# MCU.net
KiCad netlist of a schematic drawn in Altium Designer
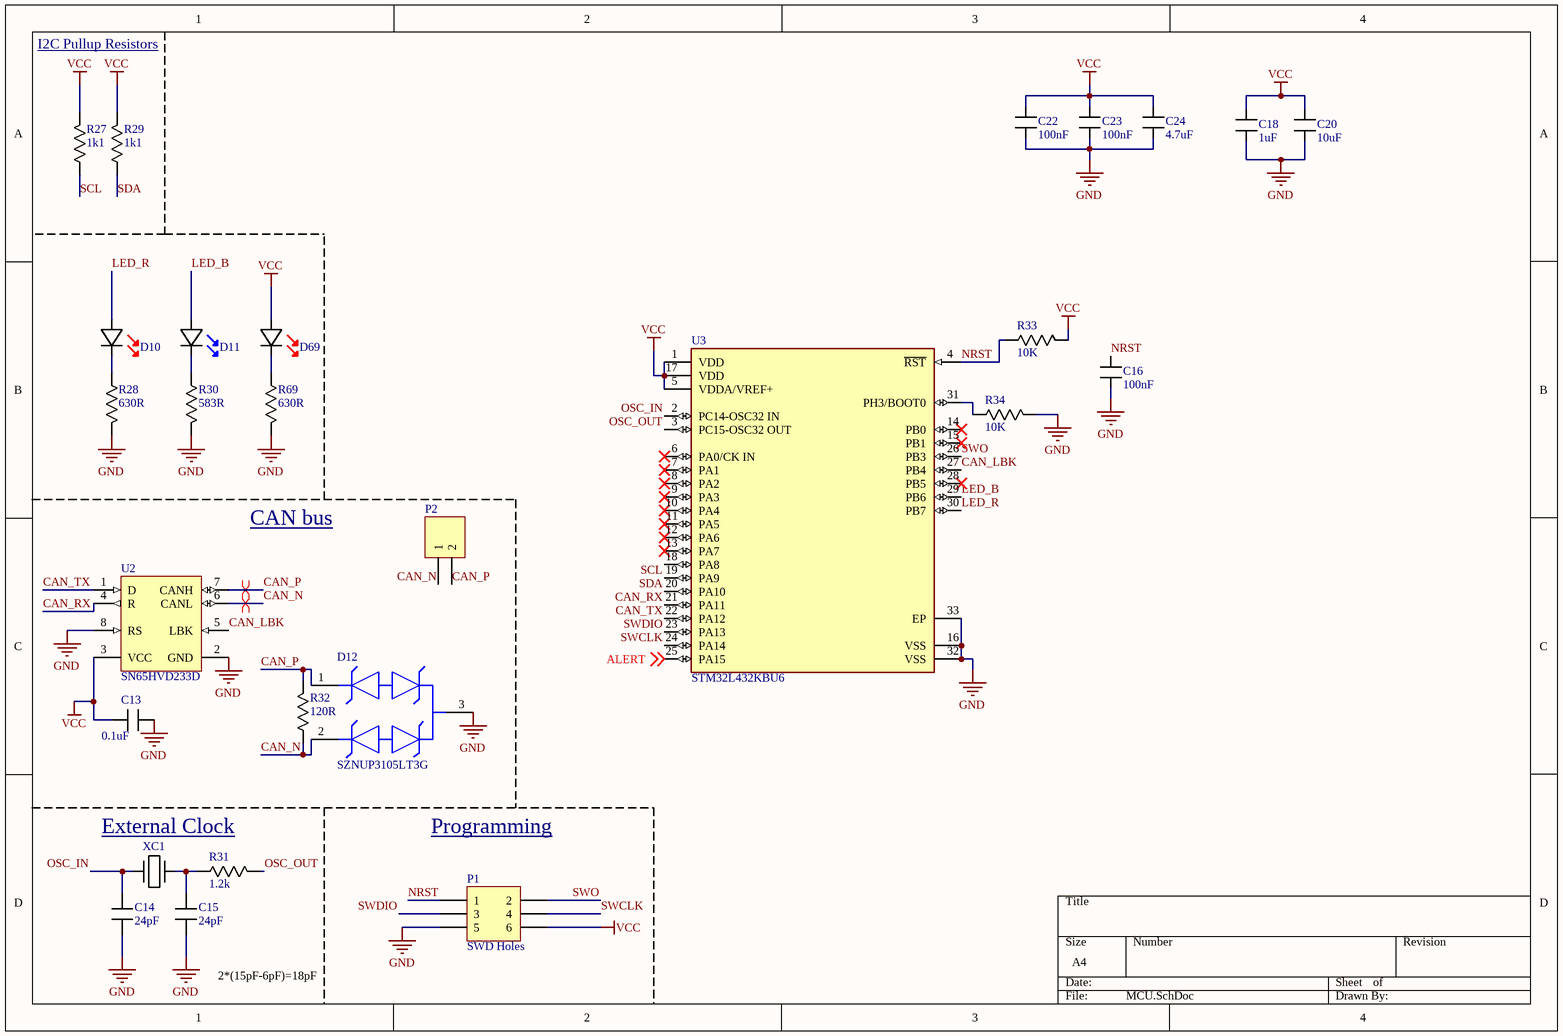
[diagram p0: MCU.SchDoc]

(export (version "E")
  (design (tool "Eeschema 10.0.6"))
  (components
    (comp (ref "C13")
      (value "0.1uF")
      (footprint "C_0603")
      (description "Capacitor")
      (fields
        (field (name "MANUFACTURER") "Kyocera AVX")
        (field (name "MANUFACTURER PART NUMBER") "06035C104JAT4A")
      )
      (libsource (lib "") (part "Capacitor_1"))
    )
    (comp (ref "C14")
      (value "24pF")
      (footprint "C_0603")
      (description "Cap Ceramic 24pF 100V C0G 1% Pad SMD 0603 125°C Ultra Low ESR T/R")
      (fields
        (field (name "MANUFACTURER") "Kyocera AVX")
        (field (name "MANUFACTURER PART NUMBER") "06031U240FAT2A")
      )
      (libsource (lib "") (part "Capacitor_1"))
    )
    (comp (ref "C15")
      (value "24pF")
      (footprint "C_0603")
      (description "Cap Ceramic 24pF 100V C0G 1% Pad SMD 0603 125°C Ultra Low ESR T/R")
      (fields
        (field (name "MANUFACTURER") "Kyocera AVX")
        (field (name "MANUFACTURER PART NUMBER") "06031U240FAT2A")
      )
      (libsource (lib "") (part "Capacitor_1"))
    )
    (comp (ref "C16")
      (value "100nF")
      (footprint "C_0603")
      (description "CAP CER 0.1UF 50V X7R 0603")
      (fields
        (field (name "MANUFACTURER") "KEMET")
        (field (name "MANUFACTURER PART NUMBER") "C0603X104K5RAC7411")
      )
      (libsource (lib "Passives") (part "Capacitor"))
    )
    (comp (ref "C18")
      (value "1uF")
      (footprint "C_0603")
      (description "Capacitor")
      (fields
        (field (name "MANUFACTURER") "KEMET")
        (field (name "MANUFACTURER PART NUMBER") "C0603C105K9RAC7411")
      )
      (libsource (lib "Passives") (part "Capacitor"))
    )
    (comp (ref "C20")
      (value "10uF")
      (footprint "C_0603")
      (description "0603, 6.3V, X5R, 10 uF ± 10 %, T&R Q200 multilayer ceramic capacitor")
      (fields
        (field (name "MANUFACTURER") "Taiyo Yuden")
        (field (name "MANUFACTURER PART NUMBER") "JMK107ABJ106KAHT")
      )
      (libsource (lib "Passives") (part "Capacitor"))
    )
    (comp (ref "C22")
      (value "100nF")
      (footprint "C_0603")
      (description "CAP CER 0.1UF 50V X7R 0603")
      (fields
        (field (name "MANUFACTURER") "KEMET")
        (field (name "MANUFACTURER PART NUMBER") "C0603X104K5RAC7411")
      )
      (libsource (lib "Passives") (part "Capacitor"))
    )
    (comp (ref "C23")
      (value "100nF")
      (footprint "C_0603")
      (description "CAP CER 0.1UF 50V X7R 0603")
      (fields
        (field (name "MANUFACTURER") "KEMET")
        (field (name "MANUFACTURER PART NUMBER") "C0603X104K5RAC7411")
      )
      (libsource (lib "Passives") (part "Capacitor"))
    )
    (comp (ref "C24")
      (value "4.7uF")
      (footprint "C_0603")
      (description "Cap Ceramic 4.7uF 6.3V X7R 10% Pad SMD 0603 125°C T/R")
      (fields
        (field (name "MANUFACTURER") "Taiyo Yuden")
        (field (name "MANUFACTURER PART NUMBER") "JMK107BB7475KA-T")
      )
      (libsource (lib "Passives") (part "Capacitor"))
    )
    (comp (ref "D10")
      (value "150060RS55040")
      (footprint "150060xS55040")
      (description "SMT Mono-color Chip LED Diffused")
      (libsource (lib "LV BMS SchLib") (part "150060RS55040"))
    )
    (comp (ref "D11")
      (value "150060BS55040")
      (footprint "150060xS55040")
      (description "LED BLUE DIFFUSED 0603 SMD")
      (fields (field (name "MANUFACTURER") "Wurth Electronics"))
      (libsource (lib "LV BMS SchLib") (part "150060BS55040"))
    )
    (comp (ref "D12")
      (value "SZNUP3105LT3G")
      (footprint "FP-318-08-MFG")
      (description "TVS DIODE 32V 66V SOT23-3")
      (fields
        (field (name "MANUFACTURER") "ON Semiconductor")
        (field (name "OCTOPART") "https://octopart.com/sznup3105lt3g-on+semiconductor-54318507")
      )
      (libsource (lib "Altium Content Vault") (part "ce38d3c06daa81fdde8c05c38ac5c9a"))
    )
    (comp (ref "D69")
      (value "150060RS55040")
      (footprint "150060xS55040")
      (description "SMT Mono-color Chip LED Diffused")
      (libsource (lib "LV BMS SchLib") (part "150060RS55040"))
    )
    (comp (ref "P1")
      (value "SWD Holes")
      (footprint "2*3 2.54mm header")
      (description "Header, 3-Pin, Dual row")
      (fields (field (name "PUBLISHER") "Altium Limited"))
      (libsource (lib "Miscellaneous Connectors") (part "MHDR2X3"))
    )
    (comp (ref "P2")
      (value "Nothing")
      (footprint "2x1 2.54MM PITCH")
      (description "Header, 2-Pin")
      (fields (field (name "PUBLISHER") "Altium Limited"))
      (libsource (lib "Miscellaneous Connectors") (part "MHDR1X2"))
    )
    (comp (ref "R27")
      (value "1k1")
      (footprint "R-0603")
      (description "Resistor")
      (fields
        (field (name "MANUFACTURER") "Vishay")
        (field (name "MANUFACTURER PART NUMBER") "CRCW06031K10JNEAC")
      )
      (libsource (lib "Passives") (part "Resistor"))
    )
    (comp (ref "R28")
      (value "630R")
      (footprint "R-0603")
      (description "High Precision-High Stability Chip Resistor Thin Film 0603 583Ohm 0.5% Paper T/R")
      (fields
        (field (name "MANUFACTURER") "Yageo")
        (field (name "MANUFACTURER PART NUMBER") "RT0603DRE07583RL")
      )
      (libsource (lib "Passives") (part "Resistor"))
    )
    (comp (ref "R29")
      (value "1k1")
      (footprint "R-0603")
      (description "Resistor")
      (fields
        (field (name "MANUFACTURER") "Vishay")
        (field (name "MANUFACTURER PART NUMBER") "CRCW06031K10JNEAC")
      )
      (libsource (lib "Passives") (part "Resistor"))
    )
    (comp (ref "R30")
      (value "583R")
      (footprint "R-0603")
      (description "High Precision-High Stability Chip Resistor Thin Film 0603 583Ohm 0.5% Paper T/R")
      (fields
        (field (name "MANUFACTURER") "Yageo")
        (field (name "MANUFACTURER PART NUMBER") "RT0603DRE07583RL")
      )
      (libsource (lib "Passives") (part "Resistor"))
    )
    (comp (ref "R31")
      (value "1.2k")
      (footprint "R-0603")
      (description "Resistor")
      (libsource (lib "Passives") (part "Resistor"))
    )
    (comp (ref "R32")
      (value "120R")
      (footprint "R-0603")
      (description "Bus termination resistor")
      (fields (field (name "Comment") "Dont populate"))
      (libsource (lib "Passives") (part "Resistor"))
    )
    (comp (ref "R33")
      (value "10K")
      (footprint "R-0603")
      (description "Resistor")
      (fields
        (field (name "MANUFACTURER") "Bourns")
        (field (name "MANUFACTURER PART NUMBER") "CMP0603AFX-1002ELF")
      )
      (libsource (lib "Passives") (part "Resistor"))
    )
    (comp (ref "R34")
      (value "10K")
      (footprint "R-0603")
      (description "Resistor")
      (fields
        (field (name "MANUFACTURER") "Bourns")
        (field (name "MANUFACTURER PART NUMBER") "CMP0603AFX-1002ELF")
      )
      (libsource (lib "Passives") (part "Resistor"))
    )
    (comp (ref "R69")
      (value "630R")
      (footprint "R-0603")
      (description "High Precision-High Stability Chip Resistor Thin Film 0603 583Ohm 0.5% Paper T/R")
      (fields
        (field (name "MANUFACTURER") "Yageo")
        (field (name "MANUFACTURER PART NUMBER") "RT0603DRE07583RL")
      )
      (libsource (lib "Passives") (part "Resistor"))
    )
    (comp (ref "U2")
      (value "SN65HVD233D")
      (footprint "D0008A_N")
      (fields (field (name "MANUFACTURER") "Texas Instruments"))
      (libsource (lib "Altium Content Vault") (part "TI-SN65HVD233-SOIC_D-8"))
    )
    (comp (ref "U3")
      (value "STM32L432KBU6")
      (footprint "FP-UFQFPN32-A0B8-MFG")
      (description "IC MCU 32BIT 128KB FLASH 32QFPN")
      (fields
        (field (name "MANUFACTURER") "STMicroelectronics")
        (field (name "OCTOPART") "https://octopart.com/stm32l432kbu6-stmicroelectronics-74568735")
      )
      (libsource (lib "Altium Content Vault") (part "2d0dd149e1b71adbded20be99a489b5"))
    )
    (comp (ref "XC1")
      (value "ATS600BSM-1E")
      (footprint "ATS600BSM-1E")
      (description "CRYSTAL 60.0000MHZ 18PF SMD")
      (fields (field (name "MANUFACTURER") "CTS") (field (name "TOLERANCE") "30ppm"))
      (libsource (lib "LV BMS SchLib") (part "ATS600BSM-1E"))
    )
  )
  (nets
    (net (code "1") (name "/CAN_LBK") (class "Default")
      (node (ref "U2") (pin "5") (pinfunction "LBK_5") (pintype "input"))
      (node (ref "U3") (pin "27") (pinfunction "PB4_27") (pintype "bidirectional"))
    )
    (net (code "2") (name "/CAN_N") (class "Default")
      (node (ref "D12") (pin "2") (pinfunction "2_2") (pintype "passive"))
      (node (ref "P2") (pin "1") (pinfunction "1_1") (pintype "passive"))
      (node (ref "R32") (pin "1") (pinfunction "1_1") (pintype "passive"))
      (node (ref "U2") (pin "6") (pinfunction "CANL_6") (pintype "bidirectional"))
    )
    (net (code "3") (name "/CAN_P") (class "Default")
      (node (ref "D12") (pin "1") (pinfunction "1_1") (pintype "passive"))
      (node (ref "P2") (pin "2") (pinfunction "2_2") (pintype "passive"))
      (node (ref "R32") (pin "2") (pinfunction "2_2") (pintype "passive"))
      (node (ref "U2") (pin "7") (pinfunction "CANH_7") (pintype "bidirectional"))
    )
    (net (code "4") (name "/CAN_RX") (class "Default")
      (node (ref "U2") (pin "4") (pinfunction "R_4") (pintype "output"))
      (node (ref "U3") (pin "21") (pinfunction "PA11_21") (pintype "bidirectional"))
    )
    (net (code "5") (name "/CAN_TX") (class "Default")
      (node (ref "U2") (pin "1") (pinfunction "D_1") (pintype "input"))
      (node (ref "U3") (pin "22") (pinfunction "PA12_22") (pintype "bidirectional"))
    )
    (net (code "6") (name "/LED_B") (class "Default")
      (node (ref "D11") (pin "2") (pinfunction "Anode_2") (pintype "passive"))
      (node (ref "U3") (pin "29") (pinfunction "PB6_29") (pintype "bidirectional"))
    )
    (net (code "7") (name "/LED_R") (class "Default")
      (node (ref "D10") (pin "2") (pinfunction "Anode_2") (pintype "passive"))
      (node (ref "U3") (pin "30") (pinfunction "PB7_30") (pintype "bidirectional"))
    )
    (net (code "8") (name "/NRST") (class "Default")
      (node (ref "C16") (pin "2") (pinfunction "2_2") (pintype "passive"))
      (node (ref "P1") (pin "1") (pinfunction "1_1") (pintype "passive"))
      (node (ref "R33") (pin "1") (pinfunction "1_1") (pintype "passive"))
      (node (ref "U3") (pin "4") (pinfunction "~{RST}_4") (pintype "input"))
    )
    (net (code "9") (name "/OSC_IN") (class "Default")
      (node (ref "C14") (pin "2") (pinfunction "2_2") (pintype "passive"))
      (node (ref "U3") (pin "2") (pinfunction "PC14-OSC32_IN_2") (pintype "bidirectional"))
      (node (ref "XC1") (pin "1") (pinfunction "1_1") (pintype "passive"))
    )
    (net (code "10") (name "/OSC_OUT") (class "Default")
      (node (ref "R31") (pin "2") (pinfunction "2_2") (pintype "passive"))
      (node (ref "U3") (pin "3") (pinfunction "PC15-OSC32_OUT_3") (pintype "bidirectional"))
    )
    (net (code "11") (name "/SCL") (class "Default")
      (node (ref "R27") (pin "1") (pinfunction "1_1") (pintype "passive"))
      (node (ref "U3") (pin "19") (pinfunction "PA9_19") (pintype "bidirectional"))
    )
    (net (code "12") (name "/SDA") (class "Default")
      (node (ref "R29") (pin "1") (pinfunction "1_1") (pintype "passive"))
      (node (ref "U3") (pin "20") (pinfunction "PA10_20") (pintype "bidirectional"))
    )
    (net (code "13") (name "/SWCLK") (class "Default")
      (node (ref "P1") (pin "4") (pinfunction "4_4") (pintype "passive"))
      (node (ref "U3") (pin "24") (pinfunction "PA14_24") (pintype "bidirectional"))
    )
    (net (code "14") (name "/SWDIO") (class "Default")
      (node (ref "P1") (pin "3") (pinfunction "3_3") (pintype "passive"))
      (node (ref "U3") (pin "23") (pinfunction "PA13_23") (pintype "bidirectional"))
    )
    (net (code "15") (name "/SWO") (class "Default")
      (node (ref "P1") (pin "2") (pinfunction "2_2") (pintype "passive"))
      (node (ref "U3") (pin "26") (pinfunction "PB3_26") (pintype "bidirectional"))
    )
    (net (code "16") (name "ALERT") (class "Default")
      (node (ref "U3") (pin "25") (pinfunction "PA15_25") (pintype "bidirectional"))
    )
    (net (code "17") (name "GND") (class "Default")
      (node (ref "C13") (pin "1") (pinfunction "1_1") (pintype "passive"))
      (node (ref "C14") (pin "1") (pinfunction "1_1") (pintype "passive"))
      (node (ref "C15") (pin "1") (pinfunction "1_1") (pintype "passive"))
      (node (ref "C16") (pin "1") (pinfunction "1_1") (pintype "passive"))
      (node (ref "C18") (pin "1") (pinfunction "1_1") (pintype "passive"))
      (node (ref "C20") (pin "1") (pinfunction "1_1") (pintype "passive"))
      (node (ref "C22") (pin "1") (pinfunction "1_1") (pintype "passive"))
      (node (ref "C23") (pin "1") (pinfunction "1_1") (pintype "passive"))
      (node (ref "C24") (pin "1") (pinfunction "1_1") (pintype "passive"))
      (node (ref "D12") (pin "3") (pinfunction "3_3") (pintype "passive"))
      (node (ref "P1") (pin "5") (pinfunction "5_5") (pintype "passive"))
      (node (ref "R28") (pin "2") (pinfunction "2_2") (pintype "passive"))
      (node (ref "R30") (pin "2") (pinfunction "2_2") (pintype "passive"))
      (node (ref "R34") (pin "2") (pinfunction "2_2") (pintype "passive"))
      (node (ref "R69") (pin "2") (pinfunction "2_2") (pintype "passive"))
      (node (ref "U2") (pin "2") (pinfunction "GND_2") (pintype "power_in"))
      (node (ref "U2") (pin "8") (pinfunction "RS_8") (pintype "input"))
      (node (ref "U3") (pin "16") (pinfunction "VSS_16") (pintype "power_in"))
      (node (ref "U3") (pin "32") (pinfunction "VSS_32") (pintype "power_in"))
      (node (ref "U3") (pin "33") (pinfunction "EP_33") (pintype "power_in"))
    )
    (net (code "18") (name "Net-(C15-Pad2)") (class "Default")
      (node (ref "C15") (pin "2") (pinfunction "2_2") (pintype "passive"))
      (node (ref "R31") (pin "1") (pinfunction "1_1") (pintype "passive"))
      (node (ref "XC1") (pin "1") (pinfunction "1_1") (pintype "passive"))
    )
    (net (code "19") (name "Net-(D10-Cathode)") (class "Default")
      (node (ref "D10") (pin "1") (pinfunction "Cathode_1") (pintype "passive"))
      (node (ref "R28") (pin "1") (pinfunction "1_1") (pintype "passive"))
    )
    (net (code "20") (name "Net-(D11-Cathode)") (class "Default")
      (node (ref "D11") (pin "1") (pinfunction "Cathode_1") (pintype "passive"))
      (node (ref "R30") (pin "1") (pinfunction "1_1") (pintype "passive"))
    )
    (net (code "21") (name "Net-(D69-Cathode)") (class "Default")
      (node (ref "D69") (pin "1") (pinfunction "Cathode_1") (pintype "passive"))
      (node (ref "R69") (pin "1") (pinfunction "1_1") (pintype "passive"))
    )
    (net (code "22") (name "Net-(U3-PH3{slash}BOOT0)") (class "Default")
      (node (ref "R34") (pin "1") (pinfunction "1_1") (pintype "passive"))
      (node (ref "U3") (pin "31") (pinfunction "PH3/BOOT0_31") (pintype "bidirectional"))
    )
    (net (code "23") (name "VCC") (class "Default")
      (node (ref "C13") (pin "2") (pinfunction "2_2") (pintype "passive"))
      (node (ref "C18") (pin "2") (pinfunction "2_2") (pintype "passive"))
      (node (ref "C20") (pin "2") (pinfunction "2_2") (pintype "passive"))
      (node (ref "C22") (pin "2") (pinfunction "2_2") (pintype "passive"))
      (node (ref "C23") (pin "2") (pinfunction "2_2") (pintype "passive"))
      (node (ref "C24") (pin "2") (pinfunction "2_2") (pintype "passive"))
      (node (ref "D69") (pin "2") (pinfunction "Anode_2") (pintype "passive"))
      (node (ref "P1") (pin "6") (pinfunction "6_6") (pintype "passive"))
      (node (ref "R27") (pin "2") (pinfunction "2_2") (pintype "passive"))
      (node (ref "R29") (pin "2") (pinfunction "2_2") (pintype "passive"))
      (node (ref "R33") (pin "2") (pinfunction "2_2") (pintype "passive"))
      (node (ref "U2") (pin "3") (pinfunction "VCC_3") (pintype "power_in"))
      (node (ref "U3") (pin "1") (pinfunction "VDD_1") (pintype "power_in"))
      (node (ref "U3") (pin "17") (pinfunction "VDD_17") (pintype "power_in"))
      (node (ref "U3") (pin "5") (pinfunction "VDDA/VREF+_5") (pintype "power_in"))
    )
    (net (code "24") (name "unconnected-(U3-PA0{slash}CK_IN-Pad6)") (class "Default")
      (node (ref "U3") (pin "6") (pinfunction "PA0/CK_IN_6") (pintype "bidirectional+no_connect"))
    )
    (net (code "25") (name "unconnected-(U3-PA1-Pad7)") (class "Default")
      (node (ref "U3") (pin "7") (pinfunction "PA1_7") (pintype "bidirectional+no_connect"))
    )
    (net (code "26") (name "unconnected-(U3-PA2-Pad8)") (class "Default")
      (node (ref "U3") (pin "8") (pinfunction "PA2_8") (pintype "bidirectional+no_connect"))
    )
    (net (code "27") (name "unconnected-(U3-PA3-Pad9)") (class "Default")
      (node (ref "U3") (pin "9") (pinfunction "PA3_9") (pintype "bidirectional+no_connect"))
    )
    (net (code "28") (name "unconnected-(U3-PA4-Pad10)") (class "Default")
      (node (ref "U3") (pin "10") (pinfunction "PA4_10") (pintype "bidirectional+no_connect"))
    )
    (net (code "29") (name "unconnected-(U3-PA5-Pad11)") (class "Default")
      (node (ref "U3") (pin "11") (pinfunction "PA5_11") (pintype "bidirectional+no_connect"))
    )
    (net (code "30") (name "unconnected-(U3-PA6-Pad12)") (class "Default")
      (node (ref "U3") (pin "12") (pinfunction "PA6_12") (pintype "bidirectional+no_connect"))
    )
    (net (code "31") (name "unconnected-(U3-PA7-Pad13)") (class "Default")
      (node (ref "U3") (pin "13") (pinfunction "PA7_13") (pintype "bidirectional+no_connect"))
    )
    (net (code "32") (name "unconnected-(U3-PA8-Pad18)") (class "Default")
      (node (ref "U3") (pin "18") (pinfunction "PA8_18") (pintype "bidirectional"))
    )
    (net (code "33") (name "unconnected-(U3-PB0-Pad14)") (class "Default")
      (node (ref "U3") (pin "14") (pinfunction "PB0_14") (pintype "bidirectional+no_connect"))
    )
    (net (code "34") (name "unconnected-(U3-PB1-Pad15)") (class "Default")
      (node (ref "U3") (pin "15") (pinfunction "PB1_15") (pintype "bidirectional+no_connect"))
    )
    (net (code "35") (name "unconnected-(U3-PB5-Pad28)") (class "Default")
      (node (ref "U3") (pin "28") (pinfunction "PB5_28") (pintype "bidirectional+no_connect"))
    )
  )
)
